# Vdd.net
KiCad netlist of a schematic drawn in Altium Designer
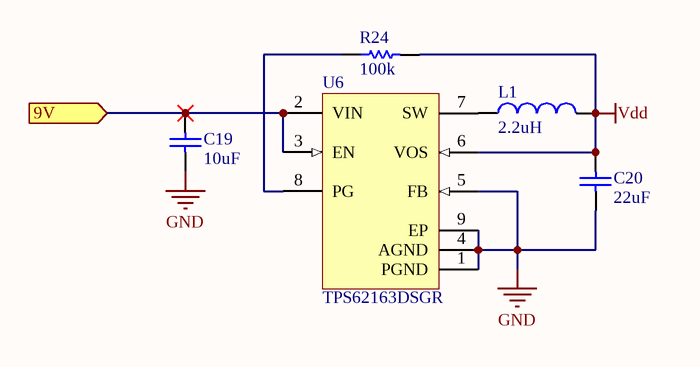
[diagram p0: Vdd.SchDoc]

(export (version "E")
  (design (tool "Eeschema 10.0.6"))
  (components
    (comp (ref "C19")
      (value "10uF")
      (footprint "C1206")
      (description "Capacitor")
      (fields (field (name "Comment") "Cap") (field (name "PUBLISHER") "Altium Limited"))
      (libsource (lib "Miscellaneous Devices") (part "Cap"))
    )
    (comp (ref "C20")
      (value "22uF")
      (footprint "C1206")
      (description "Capacitor")
      (fields (field (name "Comment") "Cap") (field (name "PUBLISHER") "Altium Limited"))
      (libsource (lib "Miscellaneous Devices") (part "Cap"))
    )
    (comp (ref "L1")
      (value "2.2uH")
      (footprint "INDC1608L")
      (description "Inductor")
      (fields (field (name "PUBLISHER") "Altium Limited"))
      (libsource (lib "Miscellaneous Devices") (part "Inductor"))
    )
    (comp (ref "R24")
      (value "100k")
      (footprint "C1206")
      (description "Resistor")
      (fields (field (name "Comment") "Res1") (field (name "PUBLISHER") "Altium Limited"))
      (libsource (lib "Miscellaneous Devices") (part "Res1"))
    )
    (comp (ref "U6")
      (value "TPS62163DSGR")
      (footprint "DSG8-1600X900TP")
      (fields (field (name "MANUFACTURER") "Texas Instruments"))
      (libsource (lib "TI Power Management Step-Down Regulator") (part "TPS62163DSGR"))
    )
  )
  (nets
    (net (code "1") (name "/9V") (class "Default")
      (node (ref "C19") (pin "2") (pinfunction "2_2") (pintype "passive"))
      (node (ref "U6") (pin "2") (pinfunction "VIN_2") (pintype "power_in"))
      (node (ref "U6") (pin "3") (pinfunction "EN_3") (pintype "input"))
    )
    (net (code "2") (name "GND") (class "Default")
      (node (ref "C19") (pin "1") (pinfunction "1_1") (pintype "passive"))
      (node (ref "C20") (pin "1") (pinfunction "1_1") (pintype "passive"))
      (node (ref "U6") (pin "1") (pinfunction "PGND_1") (pintype "power_in"))
      (node (ref "U6") (pin "4") (pinfunction "AGND_4") (pintype "power_in"))
      (node (ref "U6") (pin "5") (pinfunction "FB_5") (pintype "input"))
      (node (ref "U6") (pin "9") (pinfunction "EP_9") (pintype "power_in"))
    )
    (net (code "3") (name "Net-(U6-PG)") (class "Default")
      (node (ref "R24") (pin "1") (pinfunction "1_1") (pintype "passive"))
      (node (ref "U6") (pin "8") (pinfunction "PG_8") (pintype "tri_state"))
    )
    (net (code "4") (name "Net-(U6-SW)") (class "Default")
      (node (ref "L1") (pin "1") (pinfunction "1_1") (pintype "passive"))
      (node (ref "U6") (pin "7") (pinfunction "SW_7") (pintype "power_in"))
    )
    (net (code "5") (name "Vdd") (class "Default")
      (node (ref "C20") (pin "2") (pinfunction "2_2") (pintype "passive"))
      (node (ref "L1") (pin "2") (pinfunction "2_2") (pintype "passive"))
      (node (ref "R24") (pin "2") (pinfunction "2_2") (pintype "passive"))
      (node (ref "U6") (pin "6") (pinfunction "VOS_6") (pintype "input"))
    )
  )
)
